# schematic.net
KiCad netlist of a schematic drawn in Altium Designer
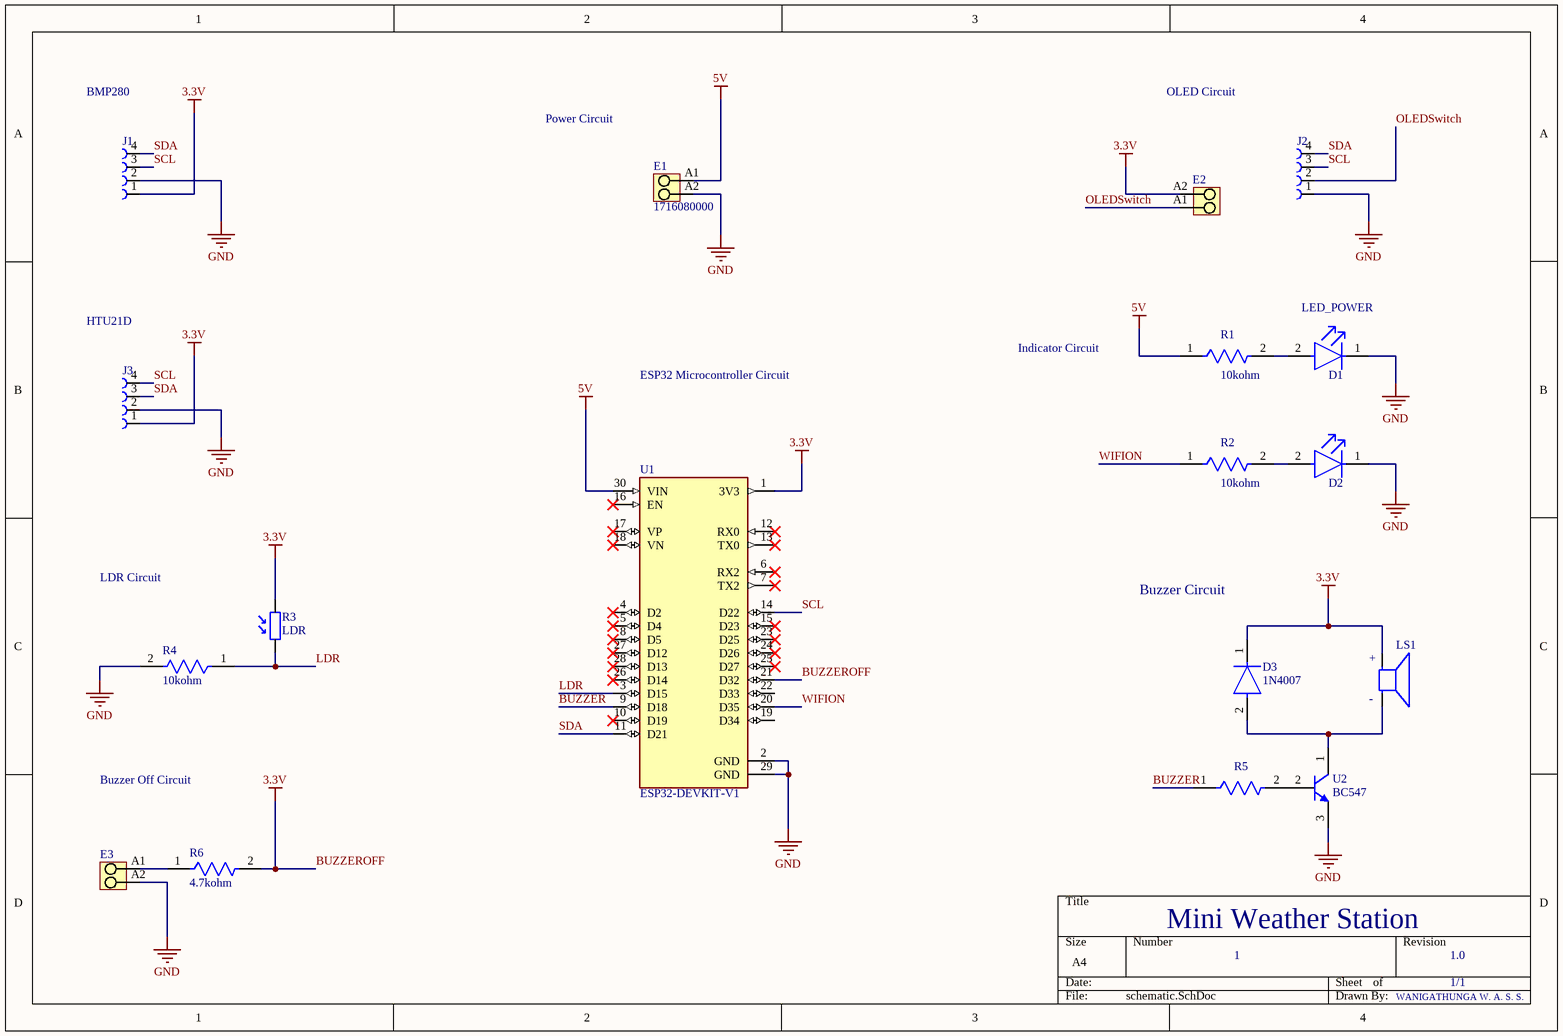
[diagram p0: schematic.SchDoc]

(export (version "E")
  (design (tool "Eeschema 10.0.6"))
  (components
    (comp (ref "D1")
      (value "LED_POWER")
      (footprint "FP-HLMP-4700-MFG")
      (description "LED RED DIFFUSED T-1 3/4 T/H")
      (fields
        (field (name "OCTOPART") "https://octopart.com/hlmp-4700-broadcom-71130526")
        (field (name "MANUFACTURER") "Broadcom")
      )
      (libsource (lib "Altium Content Vault") (part "8706943c75ba83719d021d2fdc84c58"))
    )
    (comp (ref "D2")
      (value "HLMP-4700")
      (footprint "FP-HLMP-4700-MFG")
      (description "LED RED DIFFUSED T-1 3/4 T/H")
      (fields
        (field (name "OCTOPART") "https://octopart.com/hlmp-4700-broadcom-71130526")
        (field (name "MANUFACTURER") "Broadcom")
      )
      (libsource (lib "Altium Content Vault") (part "8706943c75ba83719d021d2fdc84c58"))
    )
    (comp (ref "D3")
      (value "1N4007")
      (footprint "FP-1N4007-MFG")
      (description "DIODE GEN PURP 1KV 1A DO204AL")
      (fields
        (field (name "OCTOPART") "https://octopart.com/1n4007-e3%2F54-vishay-39548207")
        (field (name "MANUFACTURER") "Vishay")
      )
      (libsource (lib "Altium Content Vault") (part "d7152d700b627762746794eb795d46e"))
    )
    (comp (ref "E1")
      (value "1716080000")
      (footprint "LM_5_08_90_02")
      (description "OMNIMATE Signal - series LM")
      (fields (field (name "MANUFACTURER") "Weidmueller"))
      (libsource (lib "") (part "Terminal_02_1x02_1"))
    )
    (comp (ref "E2")
      (value "1716080000")
      (footprint "LM_5_08_90_02")
      (description "OMNIMATE Signal - series LM")
      (fields (field (name "MANUFACTURER") "Weidmueller"))
      (libsource (lib "Altium Content Vault") (part "Terminal_02_1x02"))
    )
    (comp (ref "E3")
      (value "1716080000")
      (footprint "LM_5_08_90_02")
      (description "OMNIMATE Signal - series LM")
      (fields (field (name "MANUFACTURER") "Weidmueller"))
      (libsource (lib "") (part "Terminal_02_1x02_1"))
    )
    (comp (ref "J1")
      (value "61300411121")
      (footprint "61300411121")
      (description "Connector Header Through Hole 4 position 0.100 (2.54mm)")
      (fields (field (name "MF") "WÃ¼rth Elektronik"))
      (libsource (lib "61300411121") (part "61300411121"))
    )
    (comp (ref "J2")
      (value "61300411121")
      (footprint "61300411121")
      (description "Connector Header Through Hole 4 position 0.100 (2.54mm)")
      (fields (field (name "MF") "WÃ¼rth Elektronik"))
      (libsource (lib "61300411121") (part "61300411121"))
    )
    (comp (ref "J3")
      (value "61300411121")
      (footprint "61300411121")
      (description "Connector Header Through Hole 4 position 0.100 (2.54mm)")
      (fields (field (name "MF") "WÃ¼rth Elektronik"))
      (libsource (lib "61300411121") (part "61300411121"))
    )
    (comp (ref "LS1")
      (value "AI-1223-TWT-5V-R")
      (footprint "XDCR_AI-1223-TWT-5V-R")
      (description "ELECTRO MECHANICAL AUDIO INDICATOR")
      (fields (field (name "MF") "PUI Audio,"))
      (libsource (lib "AI-1223-TWT-5V-R") (part "AI-1223-TWT-5V-R"))
    )
    (comp (ref "R1")
      (value "10kohm")
      (footprint "FP-CFR-25-MFG")
      (description "RES 10 OHM 1/4W 5% AXIAL")
      (fields (field (name "TOLERANCE") "5%"))
      (libsource (lib "Altium Content Vault") (part "1029c3af85768c4190bb7ad29bc67b5"))
    )
    (comp (ref "R2")
      (value "10kohm")
      (footprint "FP-CFR-25-MFG")
      (description "RES 10 OHM 1/4W 5% AXIAL")
      (fields (field (name "TOLERANCE") "5%"))
      (libsource (lib "Altium Content Vault") (part "1029c3af85768c4190bb7ad29bc67b5"))
    )
    (comp (ref "R3")
      (value "LDR")
      (footprint "NSL_19M51")
      (description "CdS Cells 550nm 20 ~ 100kOhms @ 10 lux")
      (fields (field (name "MP") "NSL-19M51") (field (name "MF") "Advanced Photonix"))
      (libsource (lib "NSL-19M51") (part "NSL-19M51"))
    )
    (comp (ref "R4")
      (value "10kohm")
      (footprint "FP-CFR-25-MFG")
      (description "RES 10 OHM 1/4W 5% AXIAL")
      (fields (field (name "TOLERANCE") "5%"))
      (libsource (lib "Altium Content Vault") (part "1029c3af85768c4190bb7ad29bc67b5"))
    )
    (comp (ref "R5")
      (value "CFR-25JB-52-10R")
      (footprint "FP-CFR-25-MFG")
      (description "RES 10 OHM 1/4W 5% AXIAL")
      (fields (field (name "TOLERANCE") "5%"))
      (libsource (lib "Altium Content Vault") (part "1029c3af85768c4190bb7ad29bc67b5"))
    )
    (comp (ref "R6")
      (value "4.7kohm")
      (footprint "FP-CFR-25-MFG")
      (description "RES 10 OHM 1/4W 5% AXIAL")
      (fields (field (name "TOLERANCE") "5%"))
      (libsource (lib "Altium Content Vault") (part "1029c3af85768c4190bb7ad29bc67b5"))
    )
    (comp (ref "U1")
      (value "ESP32-DEVKIT-V1")
      (footprint "MODULE_ESP32_DEVKIT_V1")
      (fields (field (name "MF") "Do it"))
      (libsource (lib "ESP32-DEVKIT-V1") (part "ESP32-DEVKIT-V1"))
    )
    (comp (ref "U2")
      (value "BC547")
      (footprint "ONSC-TO-92-3-29-11_AM_BL")
      (description "Amplifier Transistor, NPN Silicon, 3-Pin TO-92, Pb-Free, Tape and Reel")
      (fields (field (name "MANUFACTURER") "On Semiconductor") (field (name "PARTNUMBER") "BC547BRL1G"))
      (libsource (lib "Altium Content Vault") (part "ONSC-NPN-C1B2E3-3"))
    )
  )
  (nets
    (net (code "1") (name "/BUZZER") (class "Default")
      (node (ref "R5") (pin "1") (pinfunction "1_1") (pintype "passive"))
      (node (ref "U1") (pin "9") (pinfunction "D18_9") (pintype "bidirectional"))
    )
    (net (code "2") (name "/LDR") (class "Default")
      (node (ref "R3") (pin "1") (pinfunction "1_1") (pintype "passive"))
      (node (ref "R4") (pin "1") (pinfunction "1_1") (pintype "passive"))
      (node (ref "U1") (pin "3") (pinfunction "D15_3") (pintype "bidirectional"))
    )
    (net (code "3") (name "/OLEDSwitch") (class "Default")
      (node (ref "E2") (pin "A1") (pinfunction "A1_A1") (pintype "passive"))
      (node (ref "J2") (pin "2") (pinfunction "2_2") (pintype "passive"))
    )
    (net (code "4") (name "/SCL") (class "Default")
      (node (ref "J1") (pin "3") (pinfunction "3_3") (pintype "passive"))
      (node (ref "J2") (pin "3") (pinfunction "3_3") (pintype "passive"))
      (node (ref "J3") (pin "4") (pinfunction "4_4") (pintype "passive"))
      (node (ref "U1") (pin "14") (pinfunction "D22_14") (pintype "bidirectional"))
    )
    (net (code "5") (name "/SDA") (class "Default")
      (node (ref "J1") (pin "4") (pinfunction "4_4") (pintype "passive"))
      (node (ref "J2") (pin "4") (pinfunction "4_4") (pintype "passive"))
      (node (ref "J3") (pin "3") (pinfunction "3_3") (pintype "passive"))
      (node (ref "U1") (pin "11") (pinfunction "D21_11") (pintype "bidirectional"))
    )
    (net (code "6") (name "/WIFION") (class "Default")
      (node (ref "R2") (pin "1") (pinfunction "1_1") (pintype "passive"))
      (node (ref "U1") (pin "20") (pinfunction "D35_20") (pintype "bidirectional"))
    )
    (net (code "7") (name "3.3V") (class "Default")
      (node (ref "D3") (pin "1") (pinfunction "C_1") (pintype "passive"))
      (node (ref "E2") (pin "A2") (pinfunction "A2_A2") (pintype "passive"))
      (node (ref "J1") (pin "1") (pinfunction "1_1") (pintype "passive"))
      (node (ref "J3") (pin "1") (pinfunction "1_1") (pintype "passive"))
      (node (ref "LS1") (pin "P") (pinfunction "POS_P") (pintype "passive"))
      (node (ref "R3") (pin "2") (pinfunction "2_2") (pintype "passive"))
      (node (ref "R6") (pin "2") (pinfunction "2_2") (pintype "passive"))
      (node (ref "U1") (pin "1") (pinfunction "3V3_1") (pintype "output"))
      (node (ref "U1") (pin "21") (pinfunction "D32_21") (pintype "bidirectional"))
    )
    (net (code "8") (name "5V") (class "Default")
      (node (ref "E1") (pin "A1") (pinfunction "A1_A1") (pintype "passive"))
      (node (ref "R1") (pin "1") (pinfunction "1_1") (pintype "passive"))
      (node (ref "U1") (pin "30") (pinfunction "VIN_30") (pintype "input"))
    )
    (net (code "9") (name "GND") (class "Default")
      (node (ref "D1") (pin "1") (pinfunction "C_1") (pintype "passive"))
      (node (ref "D2") (pin "1") (pinfunction "C_1") (pintype "passive"))
      (node (ref "E1") (pin "A2") (pinfunction "A2_A2") (pintype "passive"))
      (node (ref "E3") (pin "A2") (pinfunction "A2_A2") (pintype "passive"))
      (node (ref "J1") (pin "2") (pinfunction "2_2") (pintype "passive"))
      (node (ref "J2") (pin "1") (pinfunction "1_1") (pintype "passive"))
      (node (ref "J3") (pin "2") (pinfunction "2_2") (pintype "passive"))
      (node (ref "R4") (pin "2") (pinfunction "2_2") (pintype "passive"))
      (node (ref "U1") (pin "2") (pinfunction "GND_2") (pintype "power_in"))
      (node (ref "U1") (pin "29") (pinfunction "GND_29") (pintype "power_in"))
      (node (ref "U2") (pin "3") (pinfunction "E_3") (pintype "passive"))
    )
    (net (code "10") (name "Net-(D1-A)") (class "Default")
      (node (ref "D1") (pin "2") (pinfunction "A_2") (pintype "passive"))
      (node (ref "R1") (pin "2") (pinfunction "2_2") (pintype "passive"))
    )
    (net (code "11") (name "Net-(D2-A)") (class "Default")
      (node (ref "D2") (pin "2") (pinfunction "A_2") (pintype "passive"))
      (node (ref "R2") (pin "2") (pinfunction "2_2") (pintype "passive"))
    )
    (net (code "12") (name "Net-(D3-A)") (class "Default")
      (node (ref "D3") (pin "2") (pinfunction "A_2") (pintype "passive"))
      (node (ref "LS1") (pin "N") (pinfunction "NEG_N") (pintype "passive"))
      (node (ref "U2") (pin "1") (pinfunction "C_1") (pintype "passive"))
    )
    (net (code "13") (name "Net-(E3-PadA1)") (class "Default")
      (node (ref "E3") (pin "A1") (pinfunction "A1_A1") (pintype "passive"))
      (node (ref "R6") (pin "1") (pinfunction "1_1") (pintype "passive"))
    )
    (net (code "14") (name "Net-(U2-B)") (class "Default")
      (node (ref "R5") (pin "2") (pinfunction "2_2") (pintype "passive"))
      (node (ref "U2") (pin "2") (pinfunction "B_2") (pintype "passive"))
    )
    (net (code "15") (name "unconnected-(U1-D2-Pad4)") (class "Default")
      (node (ref "U1") (pin "4") (pinfunction "D2_4") (pintype "bidirectional+no_connect"))
    )
    (net (code "16") (name "unconnected-(U1-D4-Pad5)") (class "Default")
      (node (ref "U1") (pin "5") (pinfunction "D4_5") (pintype "bidirectional+no_connect"))
    )
    (net (code "17") (name "unconnected-(U1-D5-Pad8)") (class "Default")
      (node (ref "U1") (pin "8") (pinfunction "D5_8") (pintype "bidirectional+no_connect"))
    )
    (net (code "18") (name "unconnected-(U1-D12-Pad27)") (class "Default")
      (node (ref "U1") (pin "27") (pinfunction "D12_27") (pintype "bidirectional+no_connect"))
    )
    (net (code "19") (name "unconnected-(U1-D13-Pad28)") (class "Default")
      (node (ref "U1") (pin "28") (pinfunction "D13_28") (pintype "bidirectional+no_connect"))
    )
    (net (code "20") (name "unconnected-(U1-D14-Pad26)") (class "Default")
      (node (ref "U1") (pin "26") (pinfunction "D14_26") (pintype "bidirectional+no_connect"))
    )
    (net (code "21") (name "unconnected-(U1-D19-Pad10)") (class "Default")
      (node (ref "U1") (pin "10") (pinfunction "D19_10") (pintype "bidirectional+no_connect"))
    )
    (net (code "22") (name "unconnected-(U1-D23-Pad15)") (class "Default")
      (node (ref "U1") (pin "15") (pinfunction "D23_15") (pintype "bidirectional+no_connect"))
    )
    (net (code "23") (name "unconnected-(U1-D25-Pad23)") (class "Default")
      (node (ref "U1") (pin "23") (pinfunction "D25_23") (pintype "bidirectional+no_connect"))
    )
    (net (code "24") (name "unconnected-(U1-D26-Pad24)") (class "Default")
      (node (ref "U1") (pin "24") (pinfunction "D26_24") (pintype "bidirectional+no_connect"))
    )
    (net (code "25") (name "unconnected-(U1-D27-Pad25)") (class "Default")
      (node (ref "U1") (pin "25") (pinfunction "D27_25") (pintype "bidirectional+no_connect"))
    )
    (net (code "26") (name "unconnected-(U1-D33-Pad22)") (class "Default")
      (node (ref "U1") (pin "22") (pinfunction "D33_22") (pintype "bidirectional"))
    )
    (net (code "27") (name "unconnected-(U1-D34-Pad19)") (class "Default")
      (node (ref "U1") (pin "19") (pinfunction "D34_19") (pintype "bidirectional"))
    )
    (net (code "28") (name "unconnected-(U1-EN-Pad16)") (class "Default")
      (node (ref "U1") (pin "16") (pinfunction "EN_16") (pintype "input+no_connect"))
    )
    (net (code "29") (name "unconnected-(U1-RX0-Pad12)") (class "Default")
      (node (ref "U1") (pin "12") (pinfunction "RX0_12") (pintype "input+no_connect"))
    )
    (net (code "30") (name "unconnected-(U1-RX2-Pad6)") (class "Default")
      (node (ref "U1") (pin "6") (pinfunction "RX2_6") (pintype "input+no_connect"))
    )
    (net (code "31") (name "unconnected-(U1-TX0-Pad13)") (class "Default")
      (node (ref "U1") (pin "13") (pinfunction "TX0_13") (pintype "output+no_connect"))
    )
    (net (code "32") (name "unconnected-(U1-TX2-Pad7)") (class "Default")
      (node (ref "U1") (pin "7") (pinfunction "TX2_7") (pintype "output+no_connect"))
    )
    (net (code "33") (name "unconnected-(U1-VN-Pad18)") (class "Default")
      (node (ref "U1") (pin "18") (pinfunction "VN_18") (pintype "bidirectional+no_connect"))
    )
    (net (code "34") (name "unconnected-(U1-VP-Pad17)") (class "Default")
      (node (ref "U1") (pin "17") (pinfunction "VP_17") (pintype "bidirectional+no_connect"))
    )
  )
)
